# HW1.net
KiCad netlist of a schematic drawn in Altium Designer
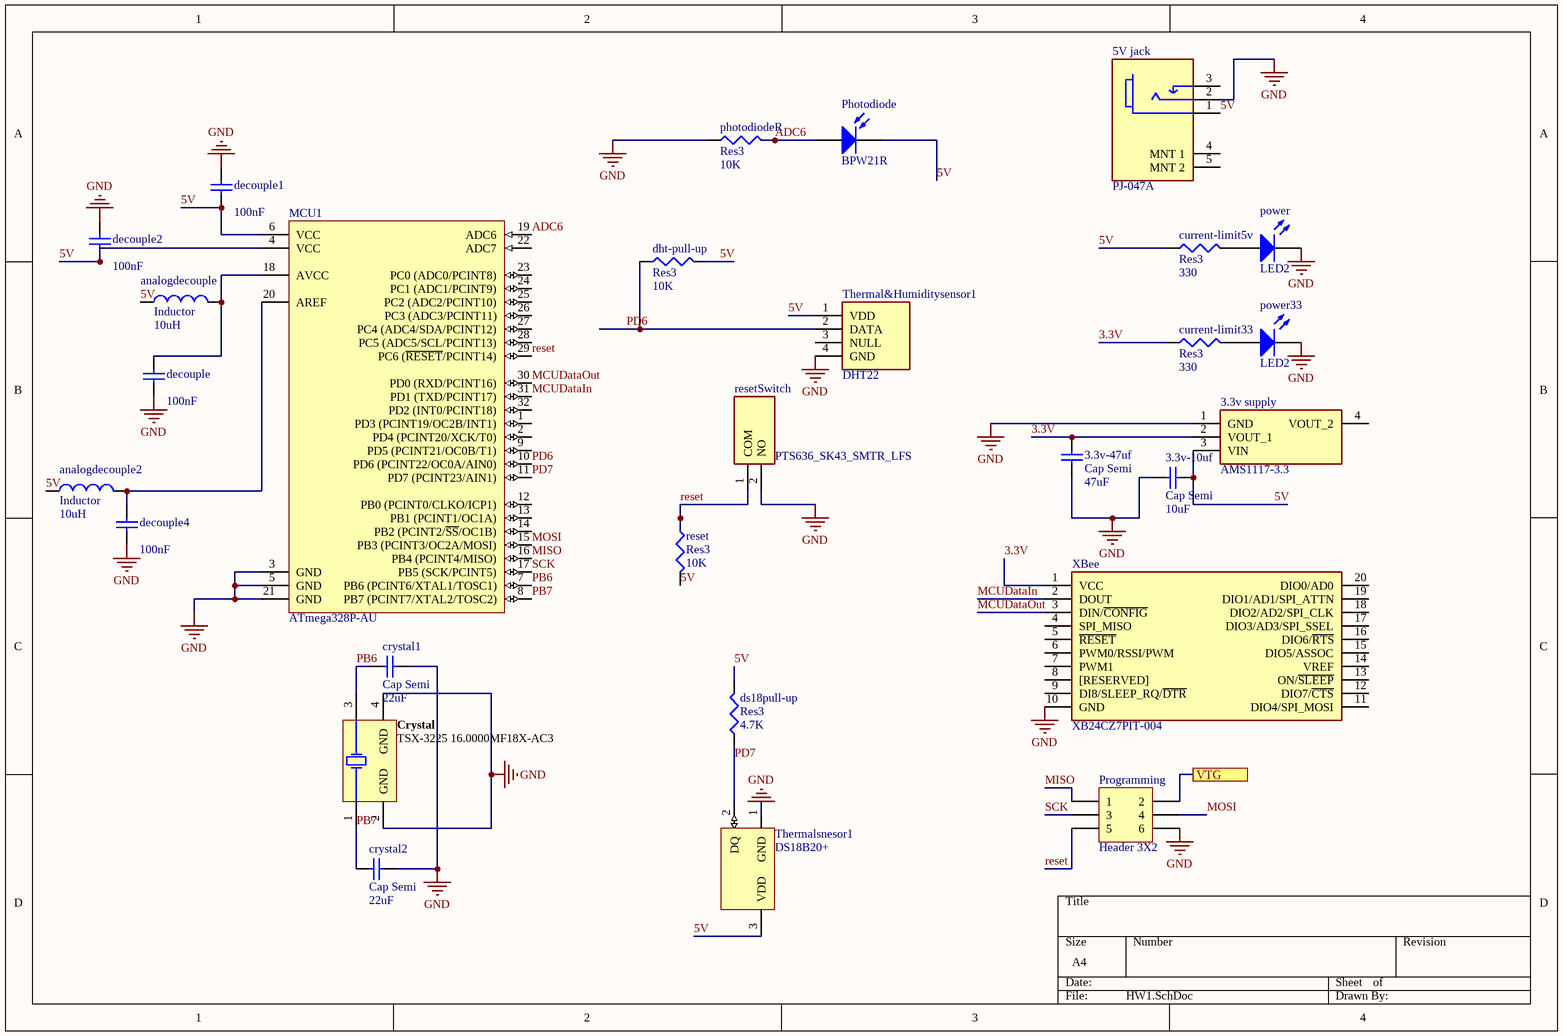
[diagram p0: HW1.SchDoc]

(export (version "E")
  (design (tool "Eeschema 10.0.6"))
  (components
    (comp (ref "3.3v supply")
      (value "AMS1117-3.3")
      (footprint "SamacSys:SOT229P700X180-4N")
      (description "Integrated Circuit")
      (libsource (lib "*") (part "AMS1117-3.3"))
    )
    (comp (ref "3.3v-10uf")
      (value "Cap Semi")
      (footprint "C1206")
      (description "Capacitor (Semiconductor SIM Model)")
      (fields (field (name "ALTIUM_VALUE") "10uF") (field (name "PUBLISHER") "Altium Limited"))
      (libsource (lib "Miscellaneous Devices") (part "Cap Semi"))
    )
    (comp (ref "3.3v-47uf")
      (value "Cap Semi")
      (footprint "C1206")
      (description "Capacitor (Semiconductor SIM Model)")
      (fields (field (name "ALTIUM_VALUE") "47uF") (field (name "PUBLISHER") "Altium Limited"))
      (libsource (lib "Miscellaneous Devices") (part "Cap Semi"))
    )
    (comp (ref "5V jack")
      (value "PJ-047A")
      (footprint "FP-PJ-047A-MFG")
      (description "CONN PWR JACK 2X5.5MM SOLDER")
      (fields
        (field (name "OCTOPART") "https://octopart.com/pj-047a-cui-19052783")
        (field (name "MANUFACTURER") "CUI Inc")
      )
      (libsource (lib "Altium Content Vault") (part "9d5a6e3f93a3d72684d180f63c174c0"))
    )
    (comp (ref "analogdecouple")
      (value "Inductor")
      (footprint "INDC1608L")
      (fields (field (name "ALTIUM_VALUE") "10uH") (field (name "PUBLISHER") "Altium Limited"))
      (libsource (lib "Miscellaneous Devices") (part "Inductor"))
    )
    (comp (ref "analogdecouple2")
      (value "Inductor")
      (footprint "INDC1608L")
      (fields (field (name "ALTIUM_VALUE") "10uH") (field (name "PUBLISHER") "Altium Limited"))
      (libsource (lib "Miscellaneous Devices") (part "Inductor"))
    )
    (comp (ref "Crystal")
      (value "TSX-3225 16.0000MF18X-AC3")
      (footprint "EPSON-TSX-3225_V")
      (description "MHz Range Crystal Unit, 16 MHz, -40 to 85 degC, 4-Pin SMD, RoHS, Tape and Reel")
      (fields (field (name "TOLERANCE") "10PPM") (field (name "MANUFACTURER") "Epson"))
      (libsource (lib "Altium Content Vault") (part "XTAL-1-3-4"))
    )
    (comp (ref "crystal1")
      (value "Cap Semi")
      (footprint "C1206")
      (description "Capacitor (Semiconductor SIM Model)")
      (fields (field (name "ALTIUM_VALUE") "22uF") (field (name "PUBLISHER") "Altium Limited"))
      (libsource (lib "Miscellaneous Devices") (part "Cap Semi"))
    )
    (comp (ref "crystal2")
      (value "Cap Semi")
      (footprint "C1206")
      (description "Capacitor (Semiconductor SIM Model)")
      (fields (field (name "ALTIUM_VALUE") "22uF") (field (name "PUBLISHER") "Altium Limited"))
      (libsource (lib "Miscellaneous Devices") (part "Cap Semi"))
    )
    (comp (ref "current-limit5v")
      (value "Res3")
      (footprint "J1-0603")
      (description "Resistor")
      (fields (field (name "ALTIUM_VALUE") "330") (field (name "PUBLISHER") "Altium Limited"))
      (libsource (lib "Miscellaneous Devices") (part "Res3"))
    )
    (comp (ref "current-limit33")
      (value "Res3")
      (footprint "J1-0603")
      (description "Resistor")
      (fields (field (name "ALTIUM_VALUE") "330") (field (name "PUBLISHER") "Altium Limited"))
      (libsource (lib "Miscellaneous Devices") (part "Res3"))
    )
    (comp (ref "decouple")
      (value "100nF")
      (footprint "C1206")
      (description "Capacitor (Semiconductor SIM Model)")
      (fields (field (name "PUBLISHER") "Altium Limited"))
      (libsource (lib "Miscellaneous Devices") (part "Cap Semi"))
    )
    (comp (ref "decouple1")
      (value "100nF")
      (footprint "C1206")
      (description "Capacitor (Semiconductor SIM Model)")
      (fields (field (name "PUBLISHER") "Altium Limited"))
      (libsource (lib "Miscellaneous Devices") (part "Cap Semi"))
    )
    (comp (ref "decouple2")
      (value "100nF")
      (footprint "C1206")
      (description "Capacitor (Semiconductor SIM Model)")
      (fields (field (name "PUBLISHER") "Altium Limited"))
      (libsource (lib "Miscellaneous Devices") (part "Cap Semi"))
    )
    (comp (ref "decouple4")
      (value "100nF")
      (footprint "C1206")
      (description "Capacitor (Semiconductor SIM Model)")
      (fields (field (name "PUBLISHER") "Altium Limited"))
      (libsource (lib "Miscellaneous Devices") (part "Cap Semi"))
    )
    (comp (ref "dht-pull-up")
      (value "Res3")
      (footprint "J1-0603")
      (description "Resistor")
      (fields (field (name "ALTIUM_VALUE") "10K") (field (name "PUBLISHER") "Altium Limited"))
      (libsource (lib "Miscellaneous Devices") (part "Res3"))
    )
    (comp (ref "ds18pull-up")
      (value "Res3")
      (footprint "J1-0603")
      (description "Resistor")
      (fields (field (name "ALTIUM_VALUE") "4.7K") (field (name "PUBLISHER") "Altium Limited"))
      (libsource (lib "Miscellaneous Devices") (part "Res3"))
    )
    (comp (ref "MCU1")
      (value "ATmega328P-AU")
      (footprint "32A_N")
      (libsource (lib "Altium Content Vault") (part "MC-8B-ATM48-SQ32"))
    )
    (comp (ref "Photodiode")
      (value "BPW21R")
      (footprint "VISH-BPW21R-2")
      (description "Silicon Photodiode, 565 nm, -40 to 125 degC, 2-Pin TO-5, RoHS, Bulk")
      (fields (field (name "MANUFACTURER") "Vishay"))
      (libsource (lib "Altium Content Vault") (part "DPTO-AK-2"))
    )
    (comp (ref "photodiodeR")
      (value "Res3")
      (footprint "J1-0603")
      (description "Resistor")
      (fields (field (name "ALTIUM_VALUE") "10K") (field (name "PUBLISHER") "Altium Limited"))
      (libsource (lib "Miscellaneous Devices") (part "Res3"))
    )
    (comp (ref "power")
      (value "LED2")
      (footprint "3.2X1.6X1.1")
      (description "Typical RED, GREEN, YELLOW, AMBER GaAs LED")
      (fields (field (name "PUBLISHER") "Altium Limited"))
      (libsource (lib "Miscellaneous Devices") (part "LED2"))
    )
    (comp (ref "power33")
      (value "LED2")
      (footprint "3.2X1.6X1.1")
      (description "Typical RED, GREEN, YELLOW, AMBER GaAs LED")
      (fields (field (name "PUBLISHER") "Altium Limited"))
      (libsource (lib "Miscellaneous Devices") (part "LED2"))
    )
    (comp (ref "Programming")
      (value "Header 3X2")
      (footprint "HDR2X3")
      (description "Header, 3-Pin, Dual row")
      (fields (field (name "PUBLISHER") "Altium Limited"))
      (libsource (lib "Miscellaneous Connectors") (part "Header 3X2"))
    )
    (comp (ref "reset")
      (value "Res3")
      (footprint "J1-0603")
      (description "Resistor")
      (fields (field (name "ALTIUM_VALUE") "10K") (field (name "PUBLISHER") "Altium Limited"))
      (libsource (lib "Miscellaneous Devices") (part "Res3"))
    )
    (comp (ref "resetSwitch")
      (value "PTS636_SK43_SMTR_LFS")
      (footprint "SamacSys:PTS636SK43SMTRLFS")
      (description "Switch")
      (fields
        (field (name "MANUFACTURER_PART_NUMBER") "PTS636 SK43 SMTR LFS")
        (field (name "MOUSER PART NUMBER") "611-PTS636SK43SMTRLF")
      )
      (libsource (lib "*") (part "PTS636_SK43_SMTR_LFS"))
    )
    (comp (ref "Thermal&Humiditysensor1")
      (value "DHT22")
      (footprint "SamacSys:DHT22")
      (description "Integrated Circuit")
      (libsource (lib "*") (part "DHT22"))
    )
    (comp (ref "Thermalsnesor1")
      (value "DS18B20+")
      (footprint "Q3+1")
      (libsource (lib "Altium Content Vault") (part "SEN-TEMP-DS1821-SIL3"))
    )
    (comp (ref "XBee")
      (value "XB24CZ7PIT-004")
      (footprint "SamacSys:XB24CAPIT-001")
      (description "Integrated Circuit")
      (fields (field (name "MOUSER PART NUMBER") "888-XB24CZ7PIT-004"))
      (libsource (lib "*") (part "XB24CZ7PIT-004"))
    )
  )
  (nets
    (net (code "1") (name "/3.3V") (class "Default")
      (node (ref "3.3v supply") (pin "2") (pinfunction "VOUT_1_2") (pintype "passive"))
      (node (ref "3.3v-47uf") (pin "2") (pinfunction "2_2") (pintype "passive"))
      (node (ref "XBee") (pin "1") (pinfunction "VCC_1") (pintype "passive"))
      (node (ref "current-limit33") (pin "1") (pinfunction "1_1") (pintype "passive"))
    )
    (net (code "2") (name "/5V") (class "Default")
      (node (ref "3.3v supply") (pin "3") (pinfunction "VIN_3") (pintype "passive"))
      (node (ref "3.3v-10uf") (pin "2") (pinfunction "2_2") (pintype "passive"))
      (node (ref "5V jack") (pin "1") (pinfunction "1_1") (pintype "passive"))
      (node (ref "MCU1") (pin "4") (pinfunction "VCC_4") (pintype "power_in"))
      (node (ref "MCU1") (pin "6") (pinfunction "VCC_6") (pintype "power_in"))
      (node (ref "Photodiode") (pin "2") (pinfunction "K_2") (pintype "passive"))
      (node (ref "Thermal&Humiditysensor1") (pin "1") (pinfunction "VDD_1") (pintype "passive"))
      (node (ref "Thermalsnesor1") (pin "3") (pinfunction "VDD_3") (pintype "power_in"))
      (node (ref "analogdecouple") (pin "1") (pinfunction "1_1") (pintype "passive"))
      (node (ref "analogdecouple2") (pin "1") (pinfunction "1_1") (pintype "passive"))
      (node (ref "current-limit5v") (pin "1") (pinfunction "1_1") (pintype "passive"))
      (node (ref "decouple1") (pin "1") (pinfunction "1_1") (pintype "passive"))
      (node (ref "decouple2") (pin "1") (pinfunction "1_1") (pintype "passive"))
      (node (ref "dht-pull-up") (pin "2") (pinfunction "2_2") (pintype "passive"))
      (node (ref "ds18pull-up") (pin "2") (pinfunction "2_2") (pintype "passive"))
      (node (ref "reset") (pin "2") (pinfunction "2_2") (pintype "passive"))
    )
    (net (code "4") (name "/ADC6") (class "Default")
      (node (ref "MCU1") (pin "19") (pinfunction "ADC6_19") (pintype "input"))
      (node (ref "Photodiode") (pin "1") (pinfunction "A_1") (pintype "passive"))
      (node (ref "photodiodeR") (pin "2") (pinfunction "2_2") (pintype "passive"))
    )
    (net (code "5") (name "/MCUDataIn") (class "Default")
      (node (ref "MCU1") (pin "31") (pinfunction "PD1_(TXD/PCINT17)_31") (pintype "bidirectional"))
      (node (ref "XBee") (pin "2") (pinfunction "DOUT_2") (pintype "passive"))
    )
    (net (code "6") (name "/MCUDataOut") (class "Default")
      (node (ref "MCU1") (pin "30") (pinfunction "PD0_(RXD/PCINT16)_30") (pintype "bidirectional"))
      (node (ref "XBee") (pin "3") (pinfunction "DIN/~{CONFIG}_3") (pintype "passive"))
    )
    (net (code "7") (name "/MISO") (class "Default")
      (node (ref "MCU1") (pin "16") (pinfunction "PB4_(PCINT4/MISO)_16") (pintype "bidirectional"))
      (node (ref "Programming") (pin "1") (pinfunction "1_1") (pintype "passive"))
    )
    (net (code "8") (name "/MOSI") (class "Default")
      (node (ref "MCU1") (pin "15") (pinfunction "PB3_(PCINT3/OC2A/MOSI)_15") (pintype "bidirectional"))
      (node (ref "Programming") (pin "4") (pinfunction "4_4") (pintype "passive"))
    )
    (net (code "9") (name "/PB6") (class "Default")
      (node (ref "Crystal") (pin "3") (pinfunction "X2_3") (pintype "passive"))
      (node (ref "MCU1") (pin "7") (pinfunction "PB6_(PCINT6/XTAL1/TOSC1)_7") (pintype "bidirectional"))
      (node (ref "crystal1") (pin "1") (pinfunction "1_1") (pintype "passive"))
    )
    (net (code "10") (name "/PB7") (class "Default")
      (node (ref "Crystal") (pin "1") (pinfunction "X1_1") (pintype "passive"))
      (node (ref "MCU1") (pin "8") (pinfunction "PB7_(PCINT7/XTAL2/TOSC2)_8") (pintype "bidirectional"))
      (node (ref "crystal2") (pin "1") (pinfunction "1_1") (pintype "passive"))
    )
    (net (code "11") (name "/PD6") (class "Default")
      (node (ref "MCU1") (pin "10") (pinfunction "PD6_(PCINT22/OC0A/AIN0)_10") (pintype "bidirectional"))
      (node (ref "Thermal&Humiditysensor1") (pin "2") (pinfunction "DATA_2") (pintype "passive"))
      (node (ref "dht-pull-up") (pin "1") (pinfunction "1_1") (pintype "passive"))
    )
    (net (code "12") (name "/PD7") (class "Default")
      (node (ref "MCU1") (pin "11") (pinfunction "PD7_(PCINT23/AIN1)_11") (pintype "bidirectional"))
      (node (ref "Thermalsnesor1") (pin "2") (pinfunction "DQ_2") (pintype "bidirectional"))
      (node (ref "ds18pull-up") (pin "1") (pinfunction "1_1") (pintype "passive"))
    )
    (net (code "13") (name "/SCK") (class "Default")
      (node (ref "MCU1") (pin "17") (pinfunction "PB5_(SCK/PCINT5)_17") (pintype "bidirectional"))
      (node (ref "Programming") (pin "3") (pinfunction "3_3") (pintype "passive"))
    )
    (net (code "14") (name "/VTG") (class "Default")
      (node (ref "Programming") (pin "2") (pinfunction "2_2") (pintype "passive"))
    )
    (net (code "15") (name "/reset") (class "Default")
      (node (ref "MCU1") (pin "29") (pinfunction "PC6_(~{RESET}/PCINT14)_29") (pintype "bidirectional"))
      (node (ref "Programming") (pin "5") (pinfunction "5_5") (pintype "passive"))
      (node (ref "reset") (pin "1") (pinfunction "1_1") (pintype "passive"))
      (node (ref "resetSwitch") (pin "1") (pinfunction "COM_1") (pintype "passive"))
    )
    (net (code "16") (name "GND") (class "Default")
      (node (ref "3.3v supply") (pin "1") (pinfunction "GND_1") (pintype "passive"))
      (node (ref "3.3v-10uf") (pin "1") (pinfunction "1_1") (pintype "passive"))
      (node (ref "3.3v-47uf") (pin "1") (pinfunction "1_1") (pintype "passive"))
      (node (ref "5V jack") (pin "2") (pinfunction "2_2") (pintype "passive"))
      (node (ref "Crystal") (pin "2") (pinfunction "GND_2") (pintype "power_in"))
      (node (ref "Crystal") (pin "4") (pinfunction "GND_4") (pintype "power_in"))
      (node (ref "MCU1") (pin "21") (pinfunction "GND_21") (pintype "power_in"))
      (node (ref "MCU1") (pin "3") (pinfunction "GND_3") (pintype "power_in"))
      (node (ref "MCU1") (pin "5") (pinfunction "GND_5") (pintype "power_in"))
      (node (ref "Programming") (pin "6") (pinfunction "6_6") (pintype "passive"))
      (node (ref "Thermal&Humiditysensor1") (pin "4") (pinfunction "GND_4") (pintype "passive"))
      (node (ref "Thermalsnesor1") (pin "1") (pinfunction "GND_1") (pintype "power_in"))
      (node (ref "XBee") (pin "10") (pinfunction "GND_10") (pintype "passive"))
      (node (ref "crystal1") (pin "2") (pinfunction "2_2") (pintype "passive"))
      (node (ref "crystal2") (pin "2") (pinfunction "2_2") (pintype "passive"))
      (node (ref "decouple") (pin "1") (pinfunction "1_1") (pintype "passive"))
      (node (ref "decouple1") (pin "2") (pinfunction "2_2") (pintype "passive"))
      (node (ref "decouple2") (pin "2") (pinfunction "2_2") (pintype "passive"))
      (node (ref "decouple4") (pin "1") (pinfunction "1_1") (pintype "passive"))
      (node (ref "photodiodeR") (pin "1") (pinfunction "1_1") (pintype "passive"))
      (node (ref "power") (pin "2") (pinfunction "K_2") (pintype "passive"))
      (node (ref "power33") (pin "2") (pinfunction "K_2") (pintype "passive"))
      (node (ref "resetSwitch") (pin "2") (pinfunction "NO_2") (pintype "passive"))
    )
    (net (code "17") (name "Net-(MCU1-AREF)") (class "Default")
      (node (ref "MCU1") (pin "20") (pinfunction "AREF_20") (pintype "passive"))
      (node (ref "analogdecouple2") (pin "2") (pinfunction "2_2") (pintype "passive"))
      (node (ref "decouple4") (pin "2") (pinfunction "2_2") (pintype "passive"))
    )
    (net (code "18") (name "Net-(MCU1-AVCC)") (class "Default")
      (node (ref "MCU1") (pin "18") (pinfunction "AVCC_18") (pintype "power_in"))
      (node (ref "analogdecouple") (pin "2") (pinfunction "2_2") (pintype "passive"))
      (node (ref "decouple") (pin "2") (pinfunction "2_2") (pintype "passive"))
    )
    (net (code "19") (name "Net-(power-A)") (class "Default")
      (node (ref "current-limit5v") (pin "2") (pinfunction "2_2") (pintype "passive"))
      (node (ref "power") (pin "1") (pinfunction "A_1") (pintype "passive"))
    )
    (net (code "20") (name "Net-(power33-A)") (class "Default")
      (node (ref "current-limit33") (pin "2") (pinfunction "2_2") (pintype "passive"))
      (node (ref "power33") (pin "1") (pinfunction "A_1") (pintype "passive"))
    )
    (net (code "21") (name "unconnected-(3.3v supply-VOUT_2-Pad4)") (class "Default")
      (node (ref "3.3v supply") (pin "4") (pinfunction "VOUT_2_4") (pintype "passive"))
    )
    (net (code "22") (name "unconnected-(5V jack-MNT_1-Pad4)") (class "Default")
      (node (ref "5V jack") (pin "4") (pinfunction "MNT_1_4") (pintype "passive"))
    )
    (net (code "23") (name "unconnected-(5V jack-MNT_2-Pad5)") (class "Default")
      (node (ref "5V jack") (pin "5") (pinfunction "MNT_2_5") (pintype "passive"))
    )
    (net (code "24") (name "unconnected-(5V jack-Pad3)") (class "Default")
      (node (ref "5V jack") (pin "3") (pinfunction "3_3") (pintype "passive"))
    )
    (net (code "25") (name "unconnected-(MCU1-ADC7-Pad22)") (class "Default")
      (node (ref "MCU1") (pin "22") (pinfunction "ADC7_22") (pintype "input"))
    )
    (net (code "26") (name "unconnected-(MCU1-PB0_(PCINT0{slash}CLKO{slash}ICP1)-Pad12)") (class "Default")
      (node (ref "MCU1") (pin "12") (pinfunction "PB0_(PCINT0/CLKO/ICP1)_12") (pintype "bidirectional"))
    )
    (net (code "27") (name "unconnected-(MCU1-PB1_(PCINT1{slash}OC1A)-Pad13)") (class "Default")
      (node (ref "MCU1") (pin "13") (pinfunction "PB1_(PCINT1/OC1A)_13") (pintype "bidirectional"))
    )
    (net (code "28") (name "unconnected-(MCU1-PB2_(PCINT2{slash}~{SS}{slash}OC1B)-Pad14)") (class "Default")
      (node (ref "MCU1") (pin "14") (pinfunction "PB2_(PCINT2/~{SS}/OC1B)_14") (pintype "bidirectional"))
    )
    (net (code "29") (name "unconnected-(MCU1-PC0_(ADC0{slash}PCINT8)-Pad23)") (class "Default")
      (node (ref "MCU1") (pin "23") (pinfunction "PC0_(ADC0/PCINT8)_23") (pintype "bidirectional"))
    )
    (net (code "30") (name "unconnected-(MCU1-PC1_(ADC1{slash}PCINT9)-Pad24)") (class "Default")
      (node (ref "MCU1") (pin "24") (pinfunction "PC1_(ADC1/PCINT9)_24") (pintype "bidirectional"))
    )
    (net (code "31") (name "unconnected-(MCU1-PC2_(ADC2{slash}PCINT10)-Pad25)") (class "Default")
      (node (ref "MCU1") (pin "25") (pinfunction "PC2_(ADC2/PCINT10)_25") (pintype "bidirectional"))
    )
    (net (code "32") (name "unconnected-(MCU1-PC3_(ADC3{slash}PCINT11)-Pad26)") (class "Default")
      (node (ref "MCU1") (pin "26") (pinfunction "PC3_(ADC3/PCINT11)_26") (pintype "bidirectional"))
    )
    (net (code "33") (name "unconnected-(MCU1-PC4_(ADC4{slash}SDA{slash}PCINT12)-Pad27)") (class "Default")
      (node (ref "MCU1") (pin "27") (pinfunction "PC4_(ADC4/SDA/PCINT12)_27") (pintype "bidirectional"))
    )
    (net (code "34") (name "unconnected-(MCU1-PC5_(ADC5{slash}SCL{slash}PCINT13)-Pad28)") (class "Default")
      (node (ref "MCU1") (pin "28") (pinfunction "PC5_(ADC5/SCL/PCINT13)_28") (pintype "bidirectional"))
    )
    (net (code "35") (name "unconnected-(MCU1-PD2_(INT0{slash}PCINT18)-Pad32)") (class "Default")
      (node (ref "MCU1") (pin "32") (pinfunction "PD2_(INT0/PCINT18)_32") (pintype "bidirectional"))
    )
    (net (code "36") (name "unconnected-(MCU1-PD3_(PCINT19{slash}OC2B{slash}INT1)-Pad1)") (class "Default")
      (node (ref "MCU1") (pin "1") (pinfunction "PD3_(PCINT19/OC2B/INT1)_1") (pintype "bidirectional"))
    )
    (net (code "37") (name "unconnected-(MCU1-PD4_(PCINT20{slash}XCK{slash}T0)-Pad2)") (class "Default")
      (node (ref "MCU1") (pin "2") (pinfunction "PD4_(PCINT20/XCK/T0)_2") (pintype "bidirectional"))
    )
    (net (code "38") (name "unconnected-(MCU1-PD5_(PCINT21{slash}OC0B{slash}T1)-Pad9)") (class "Default")
      (node (ref "MCU1") (pin "9") (pinfunction "PD5_(PCINT21/OC0B/T1)_9") (pintype "bidirectional"))
    )
    (net (code "39") (name "unconnected-(Thermal&Humiditysensor1-NULL-Pad3)") (class "Default")
      (node (ref "Thermal&Humiditysensor1") (pin "3") (pinfunction "NULL_3") (pintype "passive"))
    )
    (net (code "40") (name "unconnected-(XBee-DI8{slash}SLEEP_RQ{slash}~{DTR}-Pad9)") (class "Default")
      (node (ref "XBee") (pin "9") (pinfunction "DI8/SLEEP_RQ/~{DTR}_9") (pintype "passive"))
    )
    (net (code "41") (name "unconnected-(XBee-DIO0{slash}AD0-Pad20)") (class "Default")
      (node (ref "XBee") (pin "20") (pinfunction "DIO0/AD0_20") (pintype "passive"))
    )
    (net (code "42") (name "unconnected-(XBee-DIO1{slash}AD1{slash}SPI_ATTN-Pad19)") (class "Default")
      (node (ref "XBee") (pin "19") (pinfunction "DIO1/AD1/SPI_ATTN_19") (pintype "passive"))
    )
    (net (code "43") (name "unconnected-(XBee-DIO2{slash}AD2{slash}SPI_CLK-Pad18)") (class "Default")
      (node (ref "XBee") (pin "18") (pinfunction "DIO2/AD2/SPI_CLK_18") (pintype "passive"))
    )
    (net (code "44") (name "unconnected-(XBee-DIO3{slash}AD3{slash}SPI_SSEL-Pad17)") (class "Default")
      (node (ref "XBee") (pin "17") (pinfunction "DIO3/AD3/SPI_SSEL_17") (pintype "passive"))
    )
    (net (code "45") (name "unconnected-(XBee-DIO4{slash}SPI_MOSI-Pad11)") (class "Default")
      (node (ref "XBee") (pin "11") (pinfunction "DIO4/SPI_MOSI_11") (pintype "passive"))
    )
    (net (code "46") (name "unconnected-(XBee-DIO5{slash}ASSOC-Pad15)") (class "Default")
      (node (ref "XBee") (pin "15") (pinfunction "DIO5/ASSOC_15") (pintype "passive"))
    )
    (net (code "47") (name "unconnected-(XBee-DIO6{slash}~{RTS}-Pad16)") (class "Default")
      (node (ref "XBee") (pin "16") (pinfunction "DIO6/~{RTS}_16") (pintype "passive"))
    )
    (net (code "48") (name "unconnected-(XBee-DIO7{slash}~{CTS}-Pad12)") (class "Default")
      (node (ref "XBee") (pin "12") (pinfunction "DIO7/~{CTS}_12") (pintype "passive"))
    )
    (net (code "49") (name "unconnected-(XBee-ON{slash}~{SLEEP}-Pad13)") (class "Default")
      (node (ref "XBee") (pin "13") (pinfunction "ON/~{SLEEP}_13") (pintype "passive"))
    )
    (net (code "50") (name "unconnected-(XBee-PWM0{slash}RSSI{slash}PWM-Pad6)") (class "Default")
      (node (ref "XBee") (pin "6") (pinfunction "PWM0/RSSI/PWM_6") (pintype "passive"))
    )
    (net (code "51") (name "unconnected-(XBee-PWM1-Pad7)") (class "Default")
      (node (ref "XBee") (pin "7") (pinfunction "PWM1_7") (pintype "passive"))
    )
    (net (code "52") (name "unconnected-(XBee-SPI_MISO-Pad4)") (class "Default")
      (node (ref "XBee") (pin "4") (pinfunction "SPI_MISO_4") (pintype "passive"))
    )
    (net (code "53") (name "unconnected-(XBee-VREF-Pad14)") (class "Default")
      (node (ref "XBee") (pin "14") (pinfunction "VREF_14") (pintype "passive"))
    )
    (net (code "54") (name "unconnected-(XBee-[RESERVED]-Pad8)") (class "Default")
      (node (ref "XBee") (pin "8") (pinfunction "[RESERVED]_8") (pintype "passive"))
    )
    (net (code "55") (name "unconnected-(XBee-~{RESET}-Pad5)") (class "Default")
      (node (ref "XBee") (pin "5") (pinfunction "~{RESET}_5") (pintype "passive"))
    )
  )
)
